# lpc1102_test.net
KiCad netlist of a schematic drawn in EAGLE
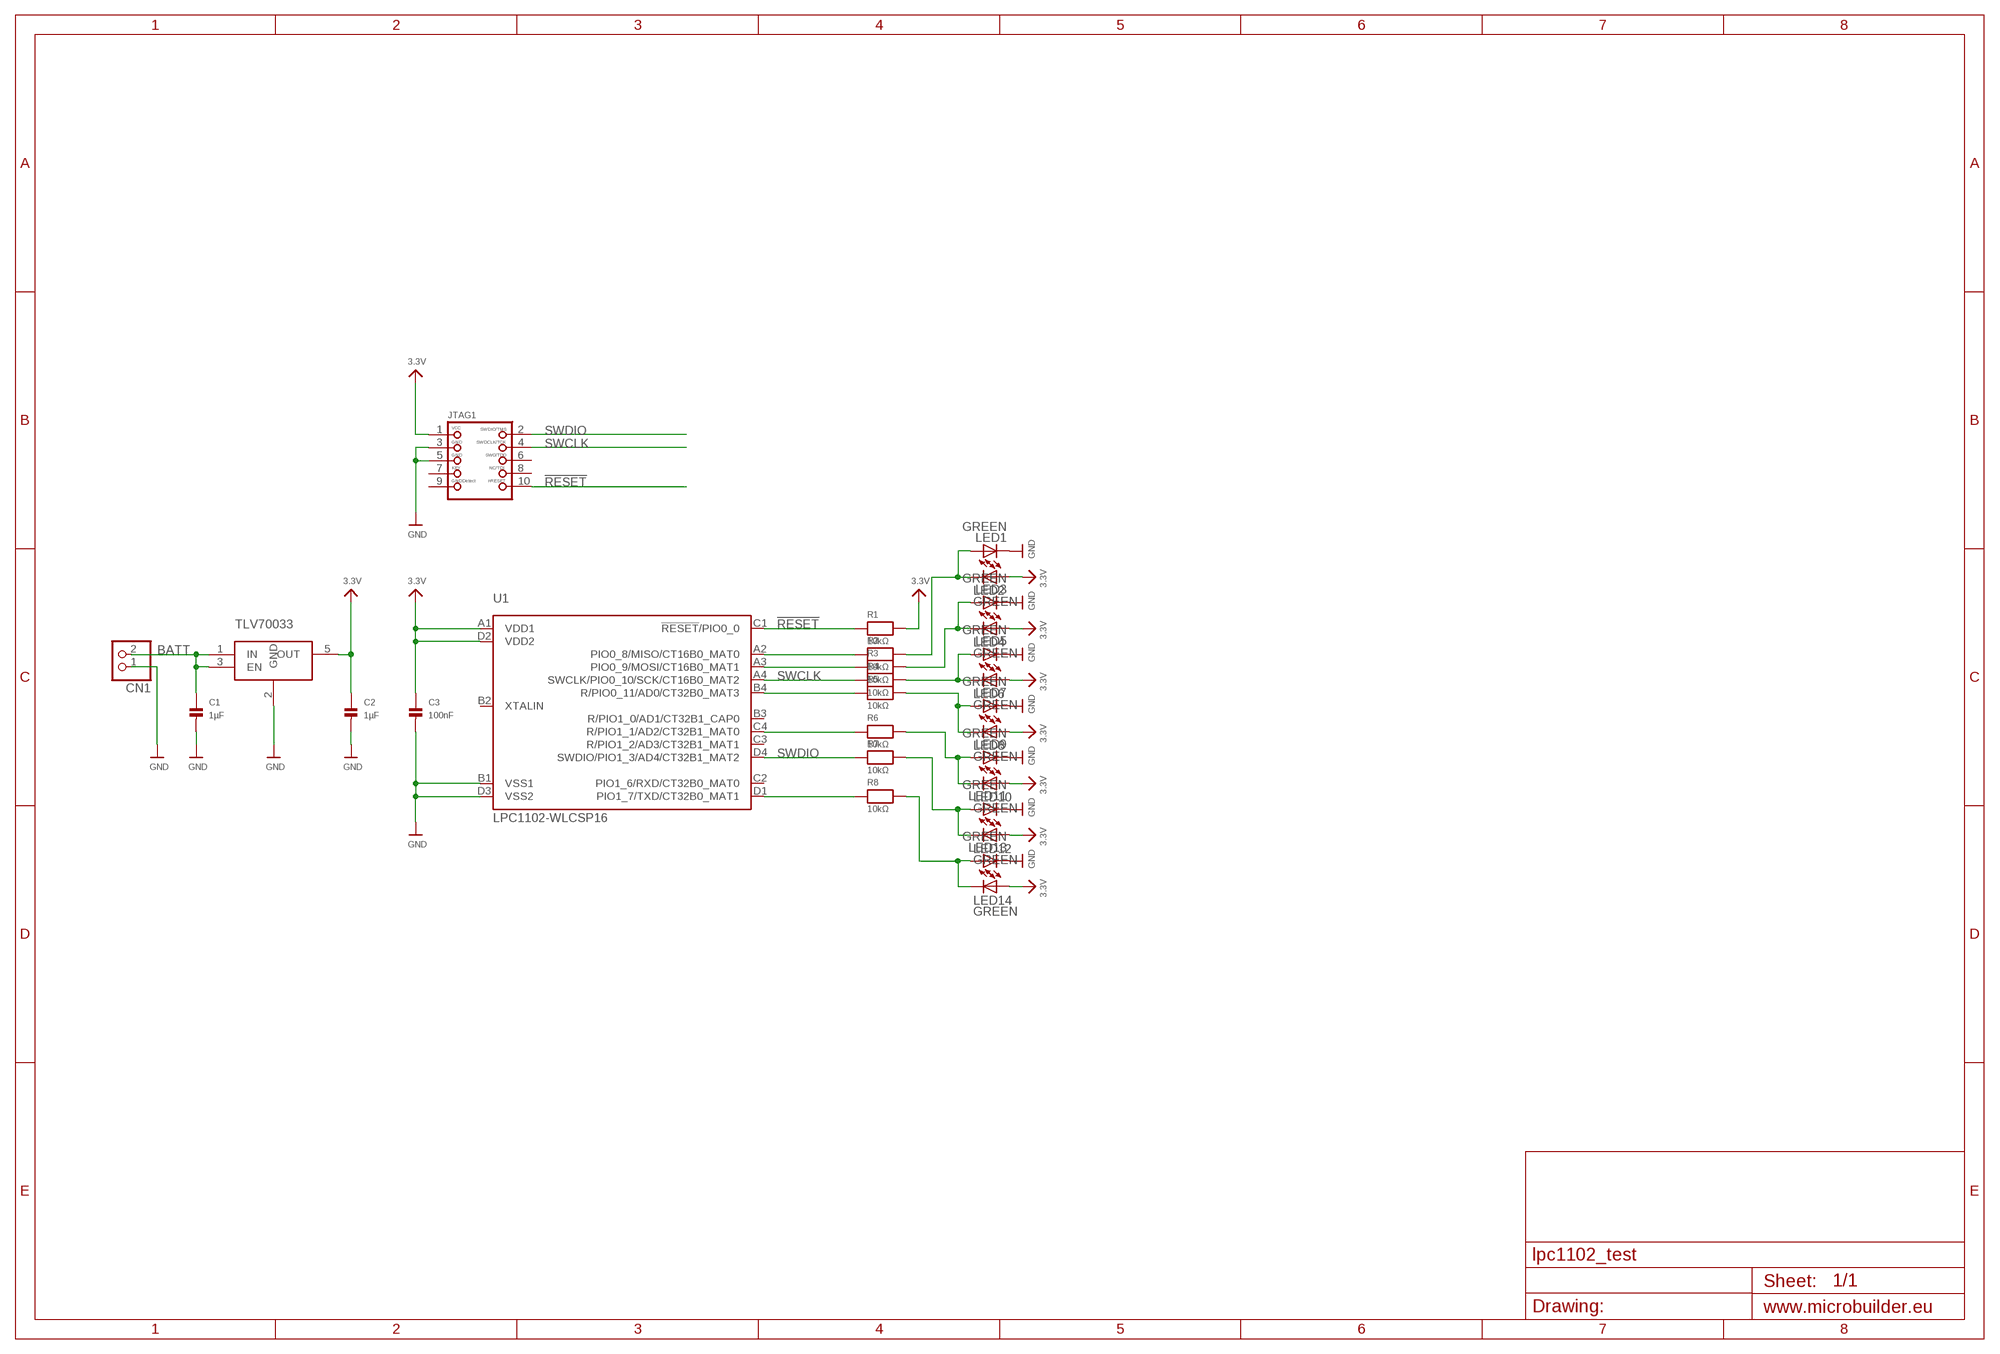
[diagram p0: schematic, sheet 1]

(export (version "E")
  (design (tool "Eeschema 10.0.6"))
  (components
    (comp (ref "C1")
      (value "1µF")
      (footprint "eagle-import:_0402")
      (libsource (lib "eagle-import") (part "CAP_CERAMIC_0402"))
    )
    (comp (ref "C2")
      (value "1µF")
      (footprint "eagle-import:_0402")
      (libsource (lib "eagle-import") (part "CAP_CERAMIC_0402"))
    )
    (comp (ref "C3")
      (value "100nF")
      (footprint "eagle-import:_0402")
      (libsource (lib "eagle-import") (part "CAP_CERAMIC_0402"))
    )
    (comp (ref "CN1")
      (value "JST_2PIN")
      (footprint "eagle-import:JSTPH2")
      (libsource (lib "eagle-import") (part "JST_2PIN"))
    )
    (comp (ref "JTAG1")
      (value "JTAG-CORTEXM3SMT")
      (footprint "eagle-import:2X05_1.27MM_SMT")
      (libsource (lib "eagle-import") (part "JTAG-CORTEXM3SMT"))
    )
    (comp (ref "LED1")
      (value "GREEN")
      (footprint "eagle-import:CHIPLED_0603")
      (libsource (lib "eagle-import") (part "LEDCHIPLED_0603"))
    )
    (comp (ref "LED2")
      (value "GREEN")
      (footprint "eagle-import:CHIPLED_0603")
      (libsource (lib "eagle-import") (part "LEDCHIPLED_0603"))
    )
    (comp (ref "LED3")
      (value "GREEN")
      (footprint "eagle-import:CHIPLED_0603")
      (libsource (lib "eagle-import") (part "LEDCHIPLED_0603"))
    )
    (comp (ref "LED4")
      (value "GREEN")
      (footprint "eagle-import:CHIPLED_0603")
      (libsource (lib "eagle-import") (part "LEDCHIPLED_0603"))
    )
    (comp (ref "LED5")
      (value "GREEN")
      (footprint "eagle-import:CHIPLED_0603")
      (libsource (lib "eagle-import") (part "LEDCHIPLED_0603"))
    )
    (comp (ref "LED6")
      (value "GREEN")
      (footprint "eagle-import:CHIPLED_0603")
      (libsource (lib "eagle-import") (part "LEDCHIPLED_0603"))
    )
    (comp (ref "LED7")
      (value "GREEN")
      (footprint "eagle-import:CHIPLED_0603")
      (libsource (lib "eagle-import") (part "LEDCHIPLED_0603"))
    )
    (comp (ref "LED8")
      (value "GREEN")
      (footprint "eagle-import:CHIPLED_0603")
      (libsource (lib "eagle-import") (part "LEDCHIPLED_0603"))
    )
    (comp (ref "LED9")
      (value "GREEN")
      (footprint "eagle-import:CHIPLED_0603")
      (libsource (lib "eagle-import") (part "LEDCHIPLED_0603"))
    )
    (comp (ref "LED10")
      (value "GREEN")
      (footprint "eagle-import:CHIPLED_0603")
      (libsource (lib "eagle-import") (part "LEDCHIPLED_0603"))
    )
    (comp (ref "LED11")
      (value "GREEN")
      (footprint "eagle-import:CHIPLED_0603")
      (libsource (lib "eagle-import") (part "LEDCHIPLED_0603"))
    )
    (comp (ref "LED12")
      (value "GREEN")
      (footprint "eagle-import:CHIPLED_0603")
      (libsource (lib "eagle-import") (part "LEDCHIPLED_0603"))
    )
    (comp (ref "LED13")
      (value "GREEN")
      (footprint "eagle-import:CHIPLED_0603")
      (libsource (lib "eagle-import") (part "LEDCHIPLED_0603"))
    )
    (comp (ref "LED14")
      (value "GREEN")
      (footprint "eagle-import:CHIPLED_0603")
      (libsource (lib "eagle-import") (part "LEDCHIPLED_0603"))
    )
    (comp (ref "R1")
      (value "10kΩ")
      (footprint "eagle-import:_0201")
      (libsource (lib "eagle-import") (part "RESISTOR_0201"))
    )
    (comp (ref "R2")
      (value "10kΩ")
      (footprint "eagle-import:_0201")
      (libsource (lib "eagle-import") (part "RESISTOR_0201"))
    )
    (comp (ref "R3")
      (value "10kΩ")
      (footprint "eagle-import:_0201")
      (libsource (lib "eagle-import") (part "RESISTOR_0201"))
    )
    (comp (ref "R4")
      (value "10kΩ")
      (footprint "eagle-import:_0201")
      (libsource (lib "eagle-import") (part "RESISTOR_0201"))
    )
    (comp (ref "R5")
      (value "10kΩ")
      (footprint "eagle-import:_0201")
      (libsource (lib "eagle-import") (part "RESISTOR_0201"))
    )
    (comp (ref "R6")
      (value "10kΩ")
      (footprint "eagle-import:_0201")
      (libsource (lib "eagle-import") (part "RESISTOR_0201"))
    )
    (comp (ref "R7")
      (value "10kΩ")
      (footprint "eagle-import:_0201")
      (libsource (lib "eagle-import") (part "RESISTOR_0201"))
    )
    (comp (ref "R8")
      (value "10kΩ")
      (footprint "eagle-import:_0201")
      (libsource (lib "eagle-import") (part "RESISTOR_0201"))
    )
    (comp (ref "U1")
      (value "LPC1102-WLCSP16")
      (footprint "eagle-import:WLCSP16")
      (libsource (lib "eagle-import") (part "LPC1102-WLCSP16"))
    )
    (comp (ref "U2")
      (value "TLV70033DCK")
      (footprint "eagle-import:SC70-5L")
      (libsource (lib "eagle-import") (part "TLV700DCK"))
    )
  )
  (nets
    (net (code "1") (name "/BATT") (class "Default")
      (node (ref "C1") (pin "1") (pinfunction "P$1_1") (pintype "passive"))
      (node (ref "CN1") (pin "2") (pinfunction "2_2") (pintype "passive"))
      (node (ref "U2") (pin "1") (pinfunction "IN_1") (pintype "bidirectional"))
      (node (ref "U2") (pin "3") (pinfunction "EN_3") (pintype "bidirectional"))
    )
    (net (code "2") (name "/SWCLK") (class "Default")
      (node (ref "JTAG1") (pin "4") (pinfunction "4_4") (pintype "passive"))
      (node (ref "R4") (pin "1") (pinfunction "1_1") (pintype "passive"))
      (node (ref "U1") (pin "A4") (pinfunction "SWCLK/PIO0_10/SCK/CT16B0_MAT2_A4") (pintype "bidirectional"))
    )
    (net (code "3") (name "/SWDIO") (class "Default")
      (node (ref "JTAG1") (pin "2") (pinfunction "2_2") (pintype "passive"))
      (node (ref "R7") (pin "1") (pinfunction "1_1") (pintype "passive"))
      (node (ref "U1") (pin "D4") (pinfunction "SWDIO/PIO1_3/AD4/CT32B1_MAT2_D4") (pintype "bidirectional"))
    )
    (net (code "4") (name "/~{RESET}") (class "Default")
      (node (ref "JTAG1") (pin "10") (pinfunction "10_10") (pintype "passive"))
      (node (ref "R1") (pin "1") (pinfunction "1_1") (pintype "passive"))
      (node (ref "U1") (pin "C1") (pinfunction "~{RESET}/PIO0_0_C1") (pintype "bidirectional"))
    )
    (net (code "5") (name "3.3V") (class "Default")
      (node (ref "C2") (pin "1") (pinfunction "P$1_1") (pintype "passive"))
      (node (ref "C3") (pin "1") (pinfunction "P$1_1") (pintype "passive"))
      (node (ref "JTAG1") (pin "1") (pinfunction "1_1") (pintype "passive"))
      (node (ref "LED10") (pin "A") (pinfunction "A_A") (pintype "passive"))
      (node (ref "LED12") (pin "A") (pinfunction "A_A") (pintype "passive"))
      (node (ref "LED14") (pin "A") (pinfunction "A_A") (pintype "passive"))
      (node (ref "LED2") (pin "A") (pinfunction "A_A") (pintype "passive"))
      (node (ref "LED4") (pin "A") (pinfunction "A_A") (pintype "passive"))
      (node (ref "LED6") (pin "A") (pinfunction "A_A") (pintype "passive"))
      (node (ref "LED8") (pin "A") (pinfunction "A_A") (pintype "passive"))
      (node (ref "R1") (pin "2") (pinfunction "2_2") (pintype "passive"))
      (node (ref "U1") (pin "A1") (pinfunction "VDD1_A1") (pintype "power_in"))
      (node (ref "U1") (pin "D2") (pinfunction "VDD2_D2") (pintype "power_in"))
      (node (ref "U2") (pin "5") (pinfunction "OUT_5") (pintype "bidirectional"))
    )
    (net (code "6") (name "GND") (class "Default")
      (node (ref "C1") (pin "2") (pinfunction "P$2_2") (pintype "passive"))
      (node (ref "C2") (pin "2") (pinfunction "P$2_2") (pintype "passive"))
      (node (ref "C3") (pin "2") (pinfunction "P$2_2") (pintype "passive"))
      (node (ref "CN1") (pin "1") (pinfunction "1_1") (pintype "passive"))
      (node (ref "JTAG1") (pin "3") (pinfunction "3_3") (pintype "passive"))
      (node (ref "JTAG1") (pin "5") (pinfunction "5_5") (pintype "passive"))
      (node (ref "LED1") (pin "C") (pinfunction "C_C") (pintype "passive"))
      (node (ref "LED11") (pin "C") (pinfunction "C_C") (pintype "passive"))
      (node (ref "LED13") (pin "C") (pinfunction "C_C") (pintype "passive"))
      (node (ref "LED3") (pin "C") (pinfunction "C_C") (pintype "passive"))
      (node (ref "LED5") (pin "C") (pinfunction "C_C") (pintype "passive"))
      (node (ref "LED7") (pin "C") (pinfunction "C_C") (pintype "passive"))
      (node (ref "LED9") (pin "C") (pinfunction "C_C") (pintype "passive"))
      (node (ref "U1") (pin "B1") (pinfunction "VSS1_B1") (pintype "power_in"))
      (node (ref "U1") (pin "D3") (pinfunction "VSS2_D3") (pintype "power_in"))
      (node (ref "U2") (pin "2") (pinfunction "GND_2") (pintype "bidirectional"))
    )
    (net (code "7") (name "Net-(LED1-PadA)") (class "Default")
      (node (ref "LED1") (pin "A") (pinfunction "A_A") (pintype "passive"))
      (node (ref "LED2") (pin "C") (pinfunction "C_C") (pintype "passive"))
      (node (ref "R2") (pin "2") (pinfunction "2_2") (pintype "passive"))
    )
    (net (code "8") (name "Net-(LED3-PadA)") (class "Default")
      (node (ref "LED3") (pin "A") (pinfunction "A_A") (pintype "passive"))
      (node (ref "LED4") (pin "C") (pinfunction "C_C") (pintype "passive"))
      (node (ref "R3") (pin "2") (pinfunction "2_2") (pintype "passive"))
    )
    (net (code "9") (name "Net-(LED5-PadA)") (class "Default")
      (node (ref "LED5") (pin "A") (pinfunction "A_A") (pintype "passive"))
      (node (ref "LED6") (pin "C") (pinfunction "C_C") (pintype "passive"))
      (node (ref "R4") (pin "2") (pinfunction "2_2") (pintype "passive"))
    )
    (net (code "10") (name "Net-(LED7-PadA)") (class "Default")
      (node (ref "LED7") (pin "A") (pinfunction "A_A") (pintype "passive"))
      (node (ref "LED8") (pin "C") (pinfunction "C_C") (pintype "passive"))
      (node (ref "R5") (pin "2") (pinfunction "2_2") (pintype "passive"))
    )
    (net (code "11") (name "Net-(LED10-PadC)") (class "Default")
      (node (ref "LED10") (pin "C") (pinfunction "C_C") (pintype "passive"))
      (node (ref "LED9") (pin "A") (pinfunction "A_A") (pintype "passive"))
      (node (ref "R6") (pin "2") (pinfunction "2_2") (pintype "passive"))
    )
    (net (code "12") (name "Net-(LED11-PadA)") (class "Default")
      (node (ref "LED11") (pin "A") (pinfunction "A_A") (pintype "passive"))
      (node (ref "LED12") (pin "C") (pinfunction "C_C") (pintype "passive"))
      (node (ref "R7") (pin "2") (pinfunction "2_2") (pintype "passive"))
    )
    (net (code "13") (name "Net-(LED13-PadA)") (class "Default")
      (node (ref "LED13") (pin "A") (pinfunction "A_A") (pintype "passive"))
      (node (ref "LED14") (pin "C") (pinfunction "C_C") (pintype "passive"))
      (node (ref "R8") (pin "2") (pinfunction "2_2") (pintype "passive"))
    )
    (net (code "14") (name "Net-(U1-PIO0_8{slash}MISO{slash}CT16B0_MAT0)") (class "Default")
      (node (ref "R2") (pin "1") (pinfunction "1_1") (pintype "passive"))
      (node (ref "U1") (pin "A2") (pinfunction "PIO0_8/MISO/CT16B0_MAT0_A2") (pintype "bidirectional"))
    )
    (net (code "15") (name "Net-(U1-PIO0_9{slash}MOSI{slash}CT16B0_MAT1)") (class "Default")
      (node (ref "R3") (pin "1") (pinfunction "1_1") (pintype "passive"))
      (node (ref "U1") (pin "A3") (pinfunction "PIO0_9/MOSI/CT16B0_MAT1_A3") (pintype "bidirectional"))
    )
    (net (code "16") (name "Net-(U1-PIO1_7{slash}TXD{slash}CT32B0_MAT1)") (class "Default")
      (node (ref "R8") (pin "1") (pinfunction "1_1") (pintype "passive"))
      (node (ref "U1") (pin "D1") (pinfunction "PIO1_7/TXD/CT32B0_MAT1_D1") (pintype "bidirectional"))
    )
    (net (code "17") (name "Net-(U1-R{slash}PIO0_11{slash}AD0{slash}CT32B0_MAT3)") (class "Default")
      (node (ref "R5") (pin "1") (pinfunction "1_1") (pintype "passive"))
      (node (ref "U1") (pin "B4") (pinfunction "R/PIO0_11/AD0/CT32B0_MAT3_B4") (pintype "bidirectional"))
    )
    (net (code "18") (name "Net-(U1-R{slash}PIO1_1{slash}AD2{slash}CT32B1_MAT0)") (class "Default")
      (node (ref "R6") (pin "1") (pinfunction "1_1") (pintype "passive"))
      (node (ref "U1") (pin "C4") (pinfunction "R/PIO1_1/AD2/CT32B1_MAT0_C4") (pintype "bidirectional"))
    )
    (net (code "19") (name "unconnected-(JTAG1-Pad6)") (class "Default")
      (node (ref "JTAG1") (pin "6") (pinfunction "6_6") (pintype "passive"))
    )
    (net (code "20") (name "unconnected-(JTAG1-Pad7)") (class "Default")
      (node (ref "JTAG1") (pin "7") (pinfunction "7_7") (pintype "passive"))
    )
    (net (code "21") (name "unconnected-(JTAG1-Pad8)") (class "Default")
      (node (ref "JTAG1") (pin "8") (pinfunction "8_8") (pintype "passive"))
    )
    (net (code "22") (name "unconnected-(JTAG1-Pad9)") (class "Default")
      (node (ref "JTAG1") (pin "9") (pinfunction "9_9") (pintype "passive"))
    )
    (net (code "23") (name "unconnected-(U1-PIO1_6{slash}RXD{slash}CT32B0_MAT0-PadC2)") (class "Default")
      (node (ref "U1") (pin "C2") (pinfunction "PIO1_6/RXD/CT32B0_MAT0_C2") (pintype "bidirectional"))
    )
    (net (code "24") (name "unconnected-(U1-R{slash}PIO1_0{slash}AD1{slash}CT32B1_CAP0-PadB3)") (class "Default")
      (node (ref "U1") (pin "B3") (pinfunction "R/PIO1_0/AD1/CT32B1_CAP0_B3") (pintype "bidirectional"))
    )
    (net (code "25") (name "unconnected-(U1-R{slash}PIO1_2{slash}AD3{slash}CT32B1_MAT1-PadC3)") (class "Default")
      (node (ref "U1") (pin "C3") (pinfunction "R/PIO1_2/AD3/CT32B1_MAT1_C3") (pintype "bidirectional"))
    )
    (net (code "26") (name "unconnected-(U1-XTALIN-PadB2)") (class "Default")
      (node (ref "U1") (pin "B2") (pinfunction "XTALIN_B2") (pintype "passive"))
    )
  )
)
